# Quadv4.net
KiCad netlist of a schematic drawn in EasyEDA
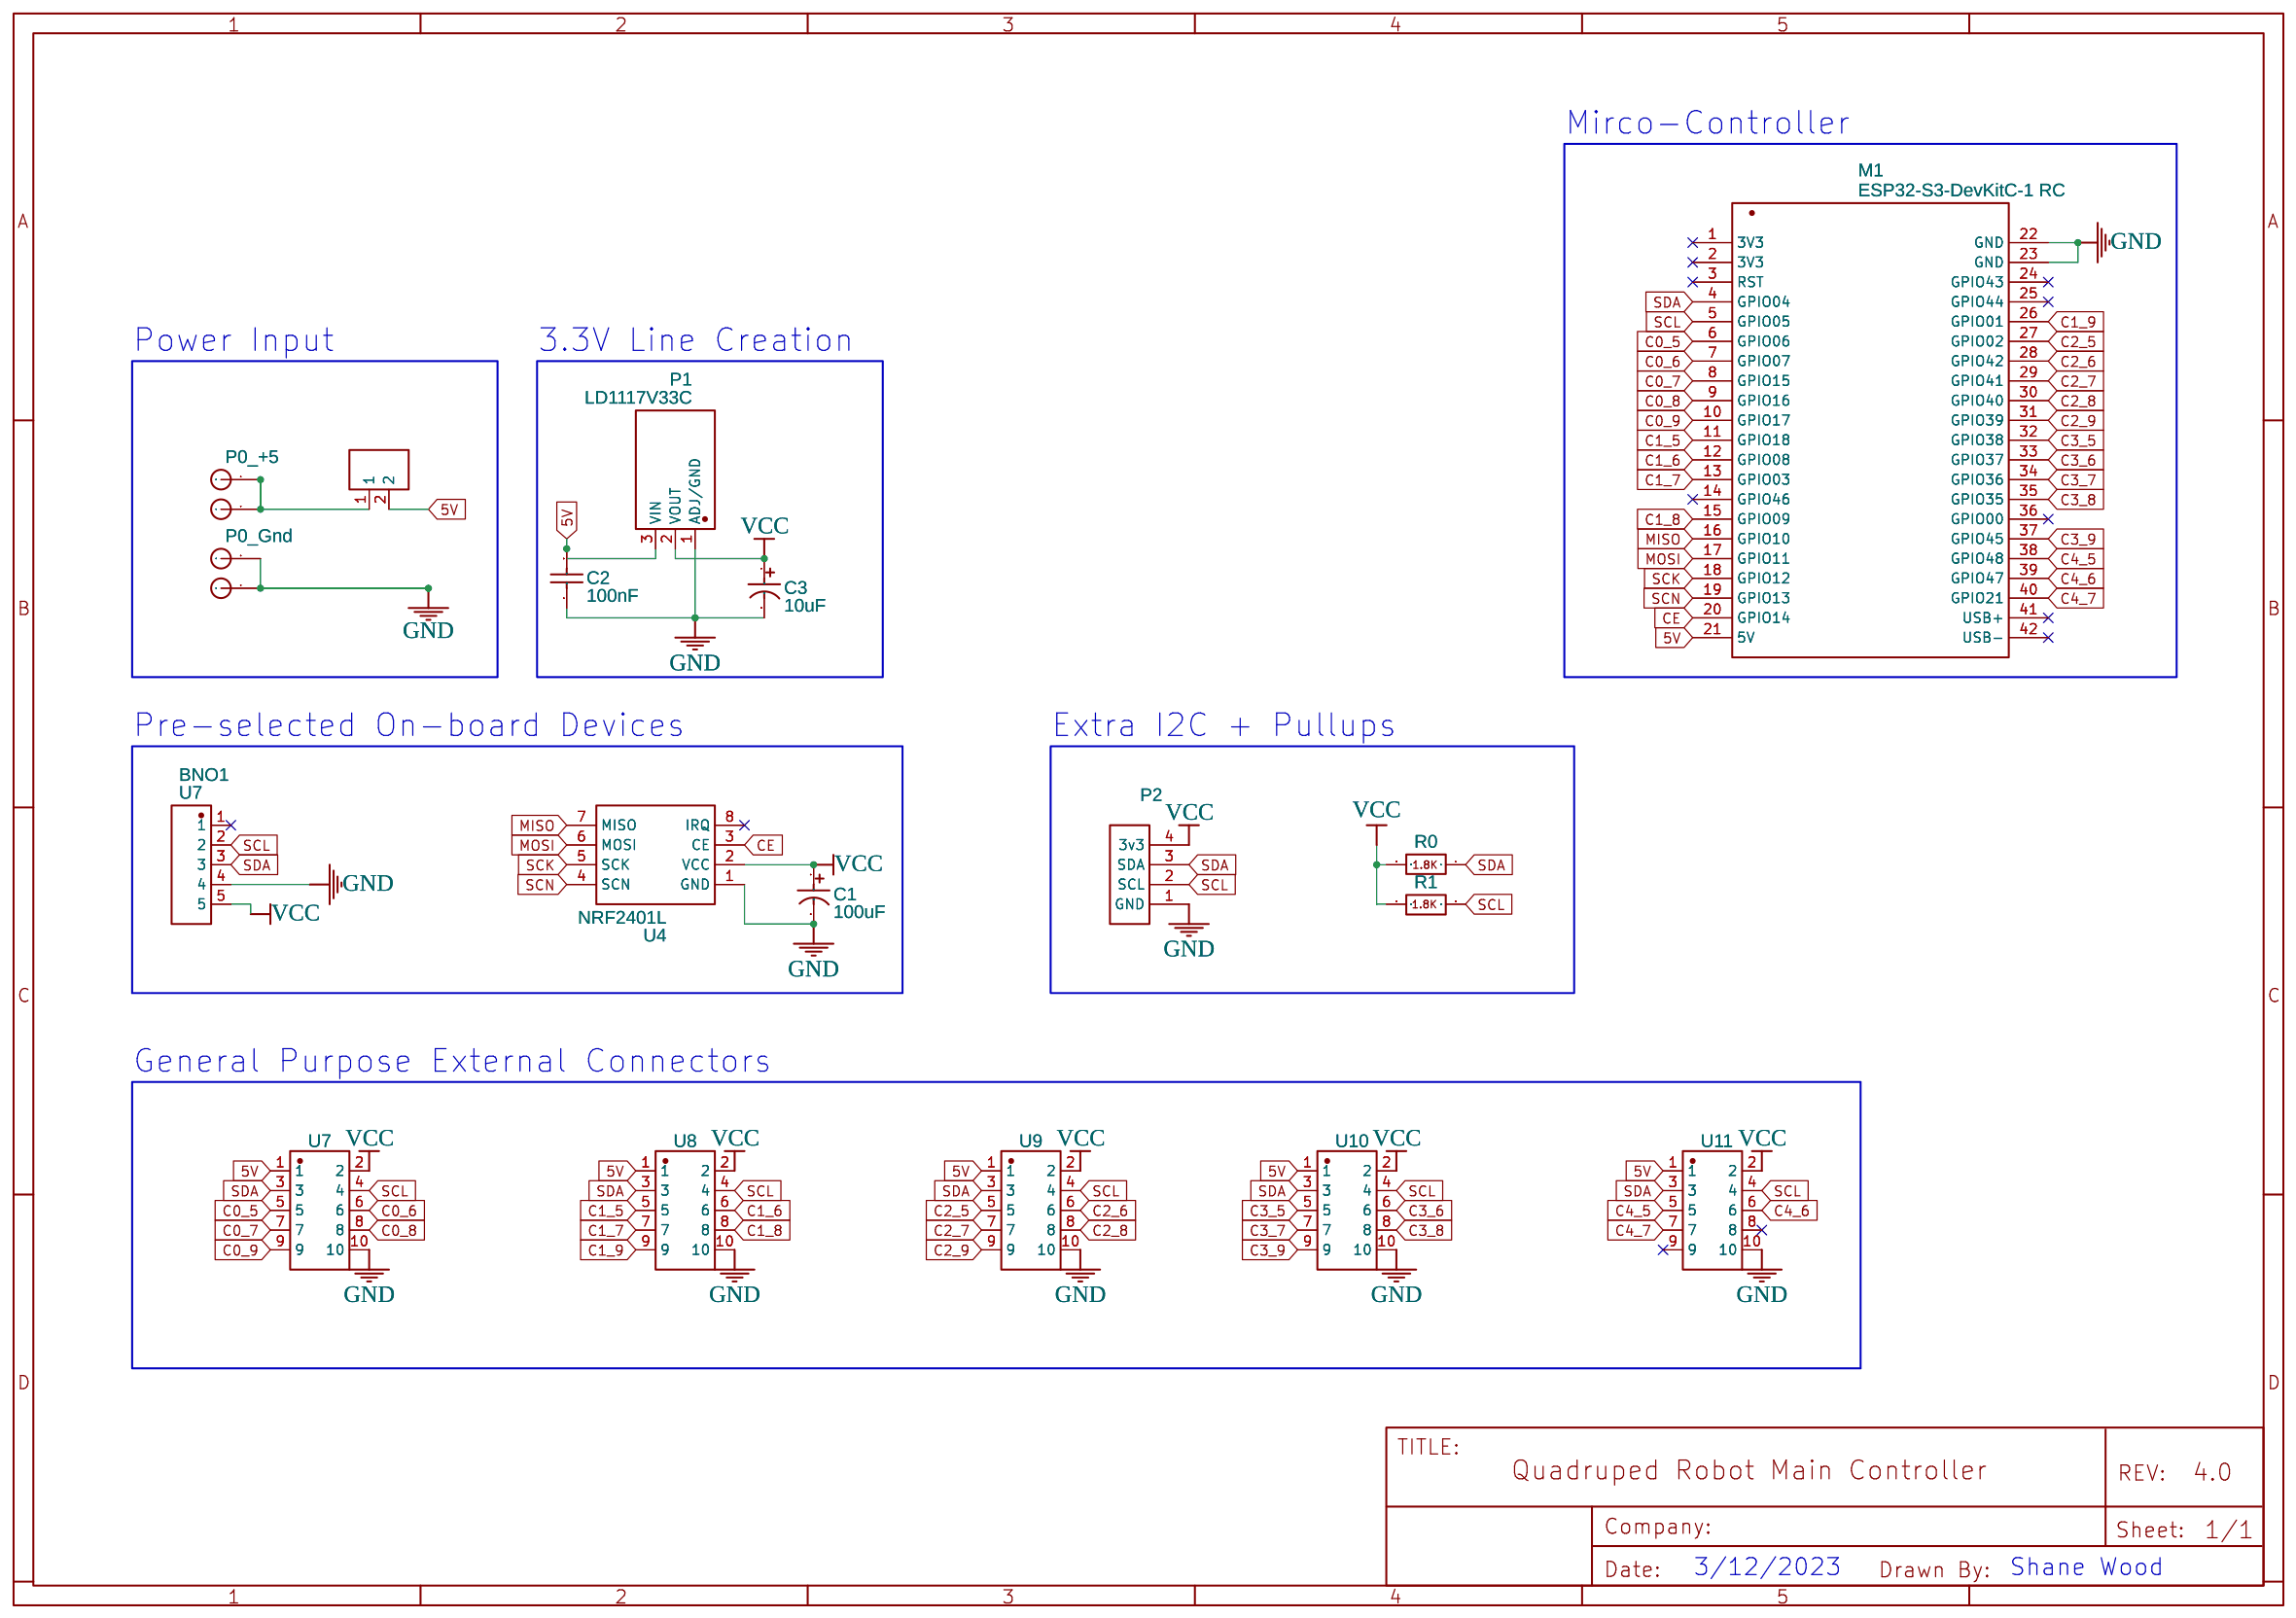
[diagram p0: schematic sheet]

(export (version "E")
  (design (tool "Eeschema 10.0.6"))
  (components
    (comp (ref "BNO1")
      (value "U7")
      (fields (field (name "Manufacturer Part") "HDR-1X5插件"))
      (libsource (lib "") (part "HDR-1X5."))
    )
    (comp (ref "C1")
      (value "100uF")
      (fields (field (name "Manufacturer Part") "Jweo"))
      (libsource (lib "") (part "CAP-POL-1"))
    )
    (comp (ref "C2")
      (value "100nF")
      (fields (field (name "Manufacturer Part") "CT4-0805Y104M500") (field (name "Manufacturer") "ReliaPro"))
      (libsource (lib "") (part "100NF COPY"))
    )
    (comp (ref "C3")
      (value "10uF")
      (fields (field (name "Manufacturer Part") "Jweo"))
      (libsource (lib "") (part "CAP 100 UF 2.5 MM KNIPEX"))
    )
    (comp (ref "M1")
      (value "ESP32-S3-DevKitC-1 RC")
      (fields
        (field (name "Manufacturer Part") "ESP32-S3-DevKitC-1")
        (field (name "Manufacturer") "Espressif Manifacturer")
      )
      (libsource (lib "") (part "ESP32-S2-DevKitC-1 RC"))
    )
    (comp (ref "P1")
      (value "LD1117V33C")
      (fields (field (name "Manufacturer") "ST(意法半导体)"))
      (libsource (lib "") (part "LD1117V33C"))
    )
    (comp (ref "P2") (value "Connector_1x4/2.5mm") (libsource (lib "") (part "Connector_1x4/2.5mm")))
    (comp (ref "P3")
      (value "Header-2.54_1x2")
      (fields (field (name "Manufacturer Part") "2.54-1*2PFemale") (field (name "Manufacturer") "BOOMELE"))
      (libsource (lib "") (part "Header-2.54_1x2"))
    )
    (comp (ref "R1") (value "R0") (libsource (lib "") (part "1.8K_R_1/2W")))
    (comp (ref "R2") (value "R1") (libsource (lib "") (part "1.8K_R_1/2W_1")))
    (comp (ref "U1")
      (value "NO")
      (fields (field (name "Manufacturer Part") "Wire Hole"))
      (libsource (lib "") (part "Wire Hole 14AWG"))
    )
    (comp (ref "U2")
      (value "P0_+5")
      (fields (field (name "Manufacturer Part") "Wire Hole"))
      (libsource (lib "") (part "Wire Hole 14AWG"))
    )
    (comp (ref "U4")
      (value "NRF2401L")
      (fields (field (name "Manufacturer Part") "nrf2401l"))
      (libsource (lib "") (part "NRF2401L"))
    )
    (comp (ref "U5")
      (value "NO")
      (fields (field (name "Manufacturer Part") "Wire Hole"))
      (libsource (lib "") (part "Wire Hole 14AWG"))
    )
    (comp (ref "U6")
      (value "P0_Gnd")
      (fields (field (name "Manufacturer Part") "Wire Hole"))
      (libsource (lib "") (part "Wire Hole 14AWG"))
    )
    (comp (ref "U7")
      (value "NO")
      (fields
        (field (name "Manufacturer Part") "KH-2.54PH180-2X5P-L8.9")
        (field (name "Manufacturer") "kinghelm(金航标)")
      )
      (libsource (lib "") (part "KH-2.54PH180-2X5P"))
    )
    (comp (ref "U8")
      (value "NO")
      (fields
        (field (name "Manufacturer Part") "KH-2.54PH180-2X5P-L8.9")
        (field (name "Manufacturer") "kinghelm(金航标)")
      )
      (libsource (lib "") (part "KH-2.54PH180-2X5P"))
    )
    (comp (ref "U9")
      (value "NO")
      (fields
        (field (name "Manufacturer Part") "KH-2.54PH180-2X5P-L8.9")
        (field (name "Manufacturer") "kinghelm(金航标)")
      )
      (libsource (lib "") (part "KH-2.54PH180-2X5P"))
    )
    (comp (ref "U10")
      (value "NO")
      (fields
        (field (name "Manufacturer Part") "KH-2.54PH180-2X5P-L8.9")
        (field (name "Manufacturer") "kinghelm(金航标)")
      )
      (libsource (lib "") (part "KH-2.54PH180-2X5P"))
    )
    (comp (ref "U11")
      (value "NO")
      (fields
        (field (name "Manufacturer Part") "KH-2.54PH180-2X5P-L8.9")
        (field (name "Manufacturer") "kinghelm(金航标)")
      )
      (libsource (lib "") (part "KH-2.54PH180-2X5P"))
    )
  )
  (nets
    (net (code "1") (name "5V") (class "Default")
      (node (ref "C2") (pin "2") (pinfunction "2_2") (pintype "input"))
      (node (ref "M1") (pin "21") (pinfunction "5V_21") (pintype "passive"))
      (node (ref "P1") (pin "3") (pinfunction "VIN_3") (pintype "unspecified"))
      (node (ref "P3") (pin "2") (pinfunction "2_2") (pintype "input"))
      (node (ref "U10") (pin "1") (pinfunction "1_1") (pintype "unspecified"))
      (node (ref "U11") (pin "1") (pinfunction "1_1") (pintype "unspecified"))
      (node (ref "U7") (pin "1") (pinfunction "1_1") (pintype "unspecified"))
      (node (ref "U8") (pin "1") (pinfunction "1_1") (pintype "unspecified"))
      (node (ref "U9") (pin "1") (pinfunction "1_1") (pintype "unspecified"))
    )
    (net (code "2") (name "C0_5") (class "Default")
      (node (ref "M1") (pin "6") (pinfunction "GPIO06_6") (pintype "bidirectional"))
      (node (ref "U7") (pin "5") (pinfunction "5_5") (pintype "unspecified"))
    )
    (net (code "3") (name "C0_6") (class "Default")
      (node (ref "M1") (pin "7") (pinfunction "GPIO07_7") (pintype "bidirectional"))
      (node (ref "U7") (pin "6") (pinfunction "6_6") (pintype "unspecified"))
    )
    (net (code "4") (name "C0_7") (class "Default")
      (node (ref "M1") (pin "8") (pinfunction "GPIO15_8") (pintype "bidirectional"))
      (node (ref "U7") (pin "7") (pinfunction "7_7") (pintype "unspecified"))
    )
    (net (code "5") (name "C0_8") (class "Default")
      (node (ref "M1") (pin "9") (pinfunction "GPIO16_9") (pintype "bidirectional"))
      (node (ref "U7") (pin "8") (pinfunction "8_8") (pintype "unspecified"))
    )
    (net (code "6") (name "C0_9") (class "Default")
      (node (ref "M1") (pin "10") (pinfunction "GPIO17_10") (pintype "bidirectional"))
      (node (ref "U7") (pin "9") (pinfunction "9_9") (pintype "unspecified"))
    )
    (net (code "7") (name "C1_5") (class "Default")
      (node (ref "M1") (pin "11") (pinfunction "GPIO18_11") (pintype "bidirectional"))
      (node (ref "U8") (pin "5") (pinfunction "5_5") (pintype "unspecified"))
    )
    (net (code "8") (name "C1_6") (class "Default")
      (node (ref "M1") (pin "12") (pinfunction "GPIO08_12") (pintype "bidirectional"))
      (node (ref "U8") (pin "6") (pinfunction "6_6") (pintype "unspecified"))
    )
    (net (code "9") (name "C1_7") (class "Default")
      (node (ref "M1") (pin "13") (pinfunction "GPIO03_13") (pintype "bidirectional"))
      (node (ref "U8") (pin "7") (pinfunction "7_7") (pintype "unspecified"))
    )
    (net (code "10") (name "C1_8") (class "Default")
      (node (ref "M1") (pin "15") (pinfunction "GPIO09_15") (pintype "bidirectional"))
      (node (ref "U8") (pin "8") (pinfunction "8_8") (pintype "unspecified"))
    )
    (net (code "11") (name "C1_9") (class "Default")
      (node (ref "M1") (pin "26") (pinfunction "GPIO01_26") (pintype "bidirectional"))
      (node (ref "U8") (pin "9") (pinfunction "9_9") (pintype "unspecified"))
    )
    (net (code "12") (name "C2_5") (class "Default")
      (node (ref "M1") (pin "27") (pinfunction "GPIO02_27") (pintype "bidirectional"))
      (node (ref "U9") (pin "5") (pinfunction "5_5") (pintype "unspecified"))
    )
    (net (code "13") (name "C2_6") (class "Default")
      (node (ref "M1") (pin "28") (pinfunction "GPIO42_28") (pintype "bidirectional"))
      (node (ref "U9") (pin "6") (pinfunction "6_6") (pintype "unspecified"))
    )
    (net (code "14") (name "C2_7") (class "Default")
      (node (ref "M1") (pin "29") (pinfunction "GPIO41_29") (pintype "bidirectional"))
      (node (ref "U9") (pin "7") (pinfunction "7_7") (pintype "unspecified"))
    )
    (net (code "15") (name "C2_8") (class "Default")
      (node (ref "M1") (pin "30") (pinfunction "GPIO40_30") (pintype "bidirectional"))
      (node (ref "U9") (pin "8") (pinfunction "8_8") (pintype "unspecified"))
    )
    (net (code "16") (name "C2_9") (class "Default")
      (node (ref "M1") (pin "31") (pinfunction "GPIO39_31") (pintype "bidirectional"))
      (node (ref "U9") (pin "9") (pinfunction "9_9") (pintype "unspecified"))
    )
    (net (code "17") (name "C3_5") (class "Default")
      (node (ref "M1") (pin "32") (pinfunction "GPIO38_32") (pintype "bidirectional"))
      (node (ref "U10") (pin "5") (pinfunction "5_5") (pintype "unspecified"))
    )
    (net (code "18") (name "C3_6") (class "Default")
      (node (ref "M1") (pin "33") (pinfunction "GPIO37_33") (pintype "bidirectional"))
      (node (ref "U10") (pin "6") (pinfunction "6_6") (pintype "unspecified"))
    )
    (net (code "19") (name "C3_7") (class "Default")
      (node (ref "M1") (pin "34") (pinfunction "GPIO36_34") (pintype "bidirectional"))
      (node (ref "U10") (pin "7") (pinfunction "7_7") (pintype "unspecified"))
    )
    (net (code "20") (name "C3_8") (class "Default")
      (node (ref "M1") (pin "35") (pinfunction "GPIO35_35") (pintype "bidirectional"))
      (node (ref "U10") (pin "8") (pinfunction "8_8") (pintype "unspecified"))
    )
    (net (code "21") (name "C3_9") (class "Default")
      (node (ref "M1") (pin "37") (pinfunction "GPIO45_37") (pintype "bidirectional"))
      (node (ref "U10") (pin "9") (pinfunction "9_9") (pintype "unspecified"))
    )
    (net (code "22") (name "C4_5") (class "Default")
      (node (ref "M1") (pin "38") (pinfunction "GPIO48_38") (pintype "bidirectional"))
      (node (ref "U11") (pin "5") (pinfunction "5_5") (pintype "unspecified"))
    )
    (net (code "23") (name "C4_6") (class "Default")
      (node (ref "M1") (pin "39") (pinfunction "GPIO47_39") (pintype "bidirectional"))
      (node (ref "U11") (pin "6") (pinfunction "6_6") (pintype "unspecified"))
    )
    (net (code "24") (name "C4_7") (class "Default")
      (node (ref "M1") (pin "40") (pinfunction "GPIO21_40") (pintype "bidirectional"))
      (node (ref "U11") (pin "7") (pinfunction "7_7") (pintype "unspecified"))
    )
    (net (code "25") (name "CE") (class "Default")
      (node (ref "M1") (pin "20") (pinfunction "GPIO14_20") (pintype "bidirectional"))
      (node (ref "U4") (pin "3") (pinfunction "CE_3") (pintype "unspecified"))
    )
    (net (code "26") (name "GND") (class "Default")
      (node (ref "BNO1") (pin "4") (pinfunction "4_4") (pintype "unspecified"))
      (node (ref "C1") (pin "2") (pinfunction "2_2") (pintype "input"))
      (node (ref "C2") (pin "1") (pinfunction "1_1") (pintype "input"))
      (node (ref "C3") (pin "2") (pinfunction "2_2") (pintype "input"))
      (node (ref "M1") (pin "22") (pinfunction "GND_22") (pintype "passive"))
      (node (ref "M1") (pin "23") (pinfunction "GND_23") (pintype "bidirectional"))
      (node (ref "P1") (pin "1") (pinfunction "ADJ/GND_1") (pintype "unspecified"))
      (node (ref "P2") (pin "1") (pinfunction "GND_1") (pintype "unspecified"))
      (node (ref "U10") (pin "10") (pinfunction "10_10") (pintype "unspecified"))
      (node (ref "U11") (pin "10") (pinfunction "10_10") (pintype "unspecified"))
      (node (ref "U4") (pin "1") (pinfunction "GND_1") (pintype "unspecified"))
      (node (ref "U5") (pin "1") (pinfunction "1_1") (pintype "unspecified"))
      (node (ref "U6") (pin "1") (pinfunction "1_1") (pintype "unspecified"))
      (node (ref "U7") (pin "10") (pinfunction "10_10") (pintype "unspecified"))
      (node (ref "U8") (pin "10") (pinfunction "10_10") (pintype "unspecified"))
      (node (ref "U9") (pin "10") (pinfunction "10_10") (pintype "unspecified"))
    )
    (net (code "27") (name "MISO") (class "Default")
      (node (ref "M1") (pin "16") (pinfunction "GPIO10_16") (pintype "bidirectional"))
      (node (ref "U4") (pin "7") (pinfunction "MISO_7") (pintype "unspecified"))
    )
    (net (code "28") (name "MOSI") (class "Default")
      (node (ref "M1") (pin "17") (pinfunction "GPIO11_17") (pintype "bidirectional"))
      (node (ref "U4") (pin "6") (pinfunction "MOSI_6") (pintype "unspecified"))
    )
    (net (code "29") (name "Net-(P3-Pad1)") (class "Default")
      (node (ref "P3") (pin "1") (pinfunction "1_1") (pintype "input"))
      (node (ref "U1") (pin "1") (pinfunction "1_1") (pintype "unspecified"))
      (node (ref "U2") (pin "1") (pinfunction "1_1") (pintype "unspecified"))
    )
    (net (code "30") (name "SCK") (class "Default")
      (node (ref "M1") (pin "18") (pinfunction "GPIO12_18") (pintype "bidirectional"))
      (node (ref "U4") (pin "5") (pinfunction "SCK_5") (pintype "unspecified"))
    )
    (net (code "31") (name "SCL") (class "Default")
      (node (ref "BNO1") (pin "2") (pinfunction "2_2") (pintype "unspecified"))
      (node (ref "M1") (pin "5") (pinfunction "GPIO05_5") (pintype "bidirectional"))
      (node (ref "P2") (pin "2") (pinfunction "SCL_2") (pintype "unspecified"))
      (node (ref "R2") (pin "2") (pinfunction "2_2") (pintype "unspecified"))
      (node (ref "U10") (pin "4") (pinfunction "4_4") (pintype "unspecified"))
      (node (ref "U11") (pin "4") (pinfunction "4_4") (pintype "unspecified"))
      (node (ref "U7") (pin "4") (pinfunction "4_4") (pintype "unspecified"))
      (node (ref "U8") (pin "4") (pinfunction "4_4") (pintype "unspecified"))
      (node (ref "U9") (pin "4") (pinfunction "4_4") (pintype "unspecified"))
    )
    (net (code "32") (name "SCN") (class "Default")
      (node (ref "M1") (pin "19") (pinfunction "GPIO13_19") (pintype "bidirectional"))
      (node (ref "U4") (pin "4") (pinfunction "SCN_4") (pintype "unspecified"))
    )
    (net (code "33") (name "SDA") (class "Default")
      (node (ref "BNO1") (pin "3") (pinfunction "3_3") (pintype "unspecified"))
      (node (ref "M1") (pin "4") (pinfunction "GPIO04_4") (pintype "bidirectional"))
      (node (ref "P2") (pin "3") (pinfunction "SDA_3") (pintype "unspecified"))
      (node (ref "R1") (pin "1") (pinfunction "1_1") (pintype "unspecified"))
      (node (ref "U10") (pin "3") (pinfunction "3_3") (pintype "unspecified"))
      (node (ref "U11") (pin "3") (pinfunction "3_3") (pintype "unspecified"))
      (node (ref "U7") (pin "3") (pinfunction "3_3") (pintype "unspecified"))
      (node (ref "U8") (pin "3") (pinfunction "3_3") (pintype "unspecified"))
      (node (ref "U9") (pin "3") (pinfunction "3_3") (pintype "unspecified"))
    )
    (net (code "34") (name "VCC") (class "Default")
      (node (ref "BNO1") (pin "5") (pinfunction "5_5") (pintype "unspecified"))
      (node (ref "C1") (pin "1") (pinfunction "1_1") (pintype "input"))
      (node (ref "C3") (pin "1") (pinfunction "1_1") (pintype "input"))
      (node (ref "P1") (pin "2") (pinfunction "VOUT_2") (pintype "unspecified"))
      (node (ref "P2") (pin "4") (pinfunction "3v3_4") (pintype "unspecified"))
      (node (ref "R1") (pin "2") (pinfunction "2_2") (pintype "unspecified"))
      (node (ref "R2") (pin "1") (pinfunction "1_1") (pintype "unspecified"))
      (node (ref "U10") (pin "2") (pinfunction "2_2") (pintype "unspecified"))
      (node (ref "U11") (pin "2") (pinfunction "2_2") (pintype "unspecified"))
      (node (ref "U4") (pin "2") (pinfunction "VCC_2") (pintype "unspecified"))
      (node (ref "U7") (pin "2") (pinfunction "2_2") (pintype "unspecified"))
      (node (ref "U8") (pin "2") (pinfunction "2_2") (pintype "unspecified"))
      (node (ref "U9") (pin "2") (pinfunction "2_2") (pintype "unspecified"))
    )
    (net (code "35") (name "unconnected-(BNO1-Pad1)") (class "Default")
      (node (ref "BNO1") (pin "1") (pinfunction "1_1") (pintype "unspecified+no_connect"))
    )
    (net (code "36") (name "unconnected-(M1-3V3-Pad1)") (class "Default")
      (node (ref "M1") (pin "1") (pinfunction "3V3_1") (pintype "passive+no_connect"))
    )
    (net (code "37") (name "unconnected-(M1-3V3-Pad2)") (class "Default")
      (node (ref "M1") (pin "2") (pinfunction "3V3_2") (pintype "passive+no_connect"))
    )
    (net (code "38") (name "unconnected-(M1-GPIO00-Pad36)") (class "Default")
      (node (ref "M1") (pin "36") (pinfunction "GPIO00_36") (pintype "input+no_connect"))
    )
    (net (code "39") (name "unconnected-(M1-GPIO43-Pad24)") (class "Default")
      (node (ref "M1") (pin "24") (pinfunction "GPIO43_24") (pintype "bidirectional+no_connect"))
    )
    (net (code "40") (name "unconnected-(M1-GPIO44-Pad25)") (class "Default")
      (node (ref "M1") (pin "25") (pinfunction "GPIO44_25") (pintype "bidirectional+no_connect"))
    )
    (net (code "41") (name "unconnected-(M1-GPIO46-Pad14)") (class "Default")
      (node (ref "M1") (pin "14") (pinfunction "GPIO46_14") (pintype "bidirectional+no_connect"))
    )
    (net (code "42") (name "unconnected-(M1-RST-Pad3)") (class "Default")
      (node (ref "M1") (pin "3") (pinfunction "RST_3") (pintype "bidirectional+no_connect"))
    )
    (net (code "43") (name "unconnected-(M1-USB+-Pad41)") (class "Default")
      (node (ref "M1") (pin "41") (pinfunction "USB+_41") (pintype "bidirectional+no_connect"))
    )
    (net (code "44") (name "unconnected-(M1-USB--Pad42)") (class "Default")
      (node (ref "M1") (pin "42") (pinfunction "USB-_42") (pintype "passive+no_connect"))
    )
    (net (code "45") (name "unconnected-(U4-IRQ-Pad8)") (class "Default")
      (node (ref "U4") (pin "8") (pinfunction "IRQ_8") (pintype "unspecified+no_connect"))
    )
    (net (code "46") (name "unconnected-(U11-Pad8)") (class "Default")
      (node (ref "U11") (pin "8") (pinfunction "8_8") (pintype "unspecified+no_connect"))
    )
    (net (code "47") (name "unconnected-(U11-Pad9)") (class "Default")
      (node (ref "U11") (pin "9") (pinfunction "9_9") (pintype "unspecified+no_connect"))
    )
  )
)
